# Schematic.net
KiCad netlist of a schematic drawn in Altium Designer
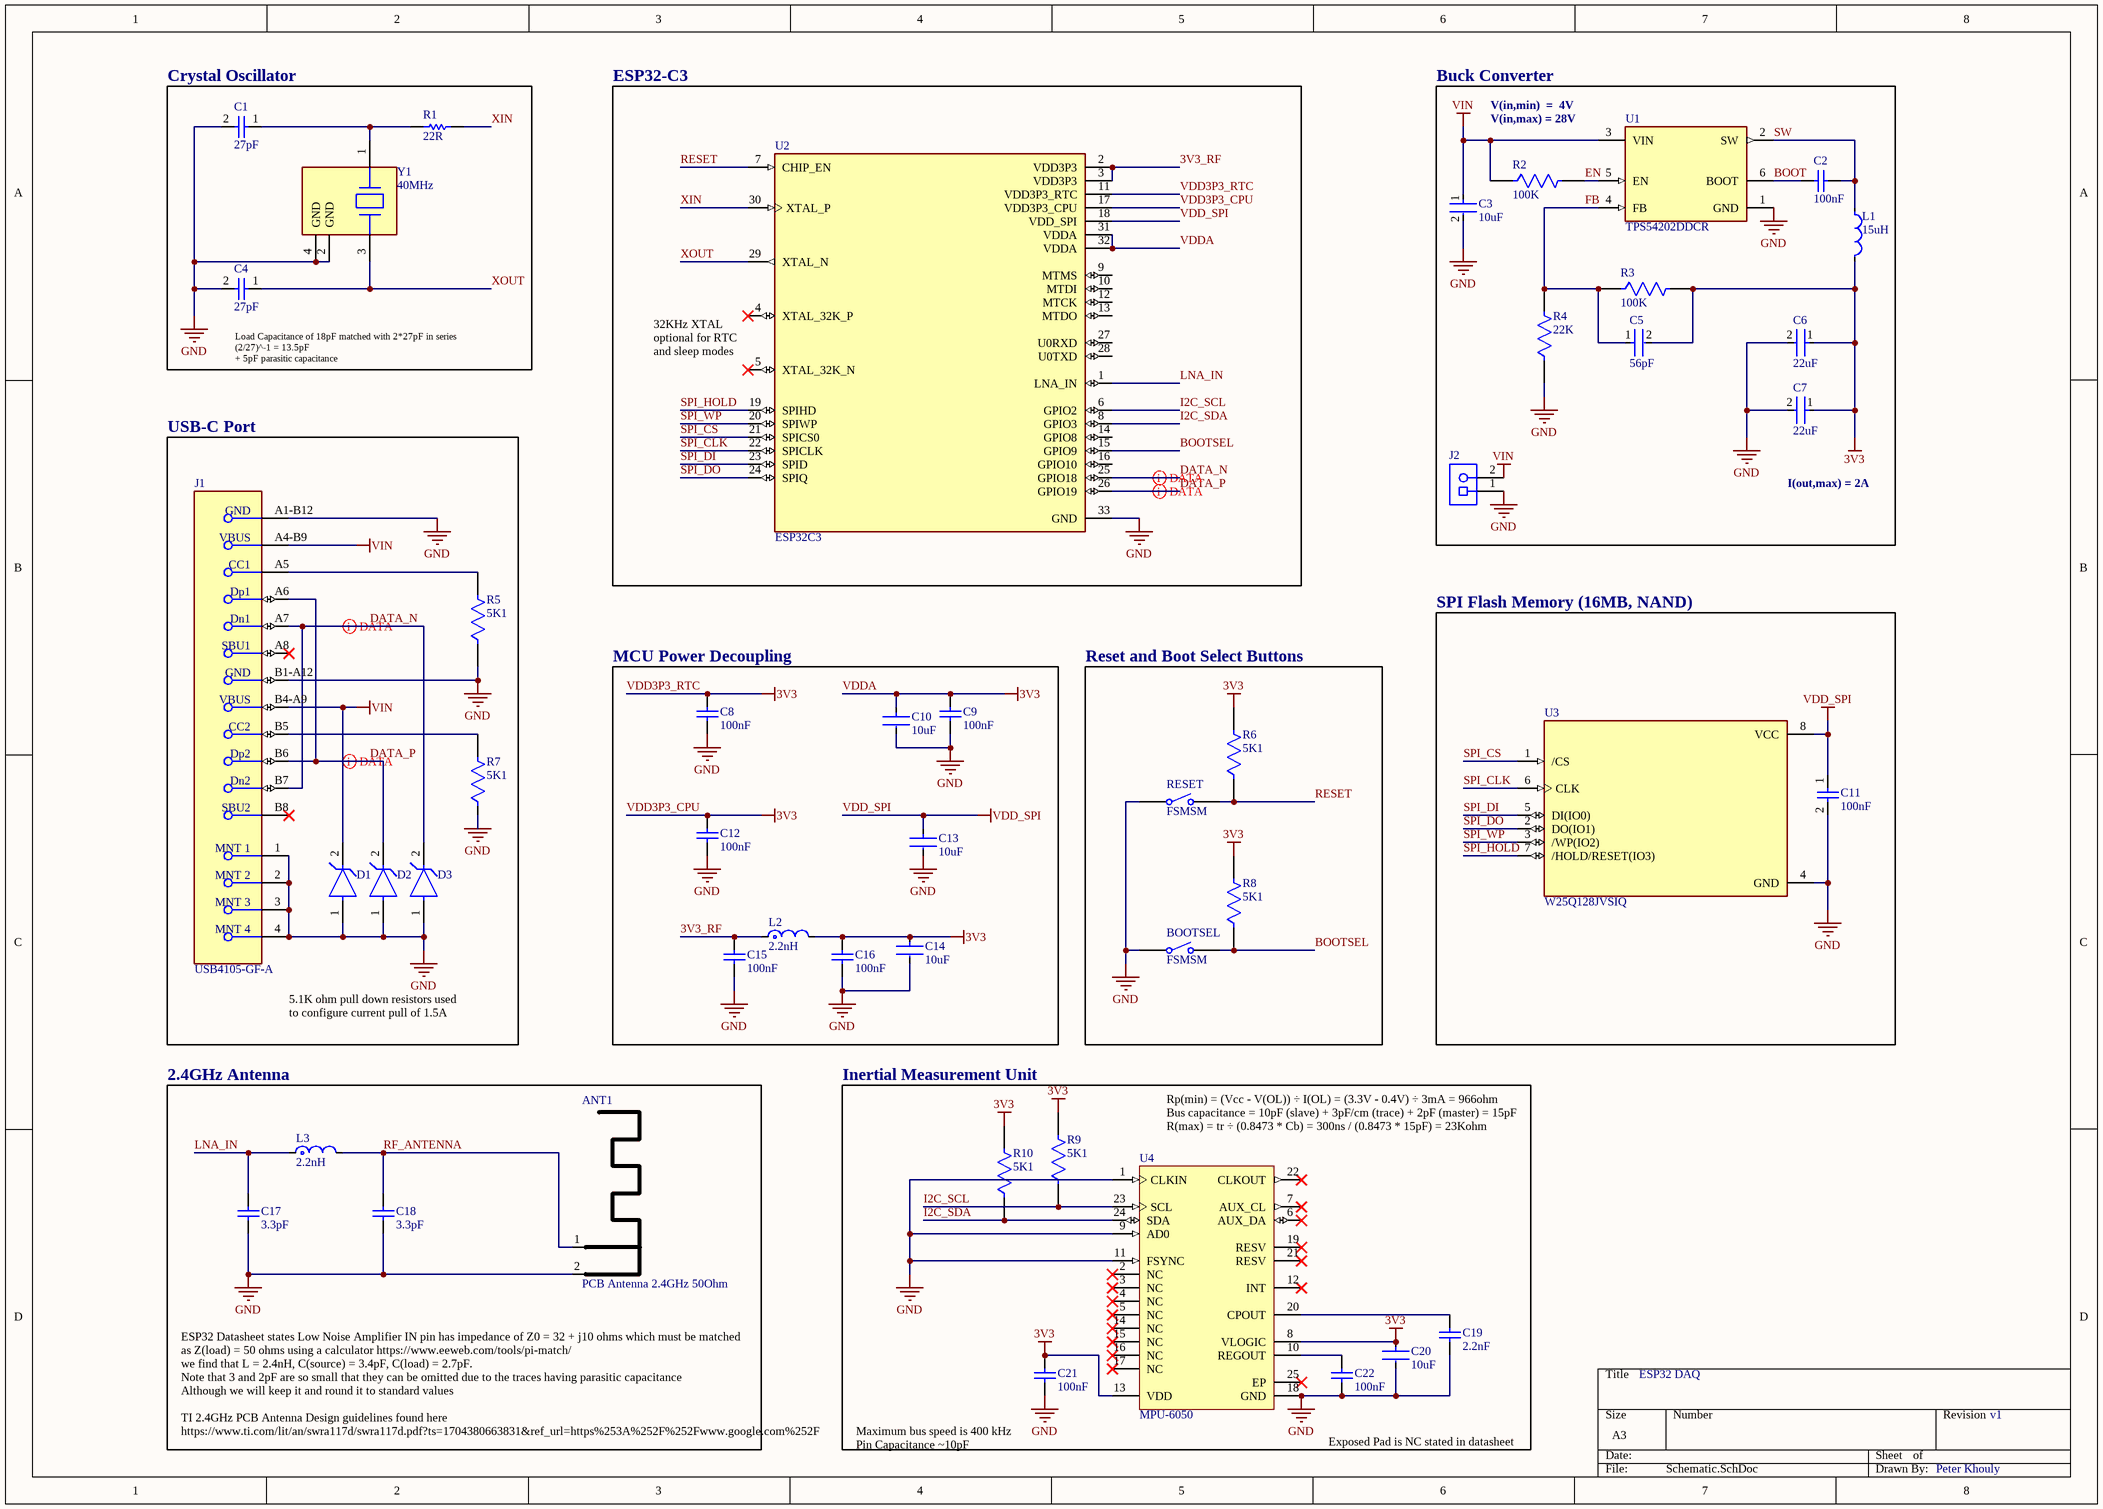
[diagram p0: Schematic.SchDoc]

(export (version "E")
  (design (tool "Eeschema 10.0.6"))
  (components
    (comp (ref "ANT1")
      (value "PCB Antenna 2.4GHz 50Ohm")
      (footprint "ANT_IFA_USB_2_4GHZ_50R")
      (description "Inverted F 2.4GHz ISM PCB Antenna 50 Ohm")
      (libsource (lib "Phils lab") (part "ANT_IFA_USB_2_4GHZ_50R"))
    )
    (comp (ref "BOOTSEL")
      (value "FSMSM")
      (footprint "TECO-FSMSM-2_V")
      (description "FSMSM Push Button Switch, 50 mA, -35 to 85 degC, 2-Pin SMD, RoHS, Bulk")
      (fields (field (name "MANUFACTURER") "TE Connectivity"))
      (libsource (lib "Altium Content Vault") (part "SW-SPST-2_C"))
    )
    (comp (ref "C1")
      (value "27pF")
      (footprint "CAPC1005X55X25LL05T10")
      (fields (field (name "PART NUMBER") "GRM1555C1H270JA01D") (field (name "MANUFACTURER") "Murata"))
      (libsource (lib "") (part "CAP_1"))
    )
    (comp (ref "C2")
      (value "100nF")
      (footprint "CAPC1005X56X25LL10T15")
      (fields
        (field (name "MANUFACTURER") "AVX Interconnect / Elco")
        (field (name "PART NUMBER") "04026D104KAT2A")
      )
      (libsource (lib "Altium Content Vault") (part "CAP"))
    )
    (comp (ref "C3")
      (value "10uF")
      (footprint "FP-GRM15-0_2-MFG")
      (description "CAP CER 10UF 6.3V X6S 0402")
      (fields (field (name "TOLERANCE") "20%") (field (name "MANUFACTURER PART NUMBER") "GRM155C80J106ME11D"))
      (libsource (lib "") (part "b4654b650e69147ec39a6b967a45e02_1"))
    )
    (comp (ref "C4")
      (value "27pF")
      (footprint "CAPC1005X55X25LL05T10")
      (fields (field (name "PART NUMBER") "GRM1555C1H270JA01D") (field (name "MANUFACTURER") "Murata"))
      (libsource (lib "") (part "CAP_1"))
    )
    (comp (ref "C5")
      (value "56pF")
      (footprint "FP-0402-L_1_0_1-W_0_5_0_1-MFG")
      (description "General Purpose Ceramic Capacitor, 0402, 56pF, 5%, C0G, 30ppm/°C, 50V")
      (fields (field (name "TOLERANCE") "5%") (field (name "VOLTAGE") "50V"))
      (libsource (lib "") (part "b4654b650e69147ec39a6b967a45e02_1"))
    )
    (comp (ref "C6")
      (value "22uF")
      (footprint "FP-CL746-IPC_C")
      (description "Cap Ceramic 22uF 6.3V X5R ±20% SMD 0402 +85°C Paper T/R")
      (fields (field (name "TOLERANCE") "20%"))
      (libsource (lib "") (part "b4654b650e69147ec39a6b967a45e02_1"))
    )
    (comp (ref "C7")
      (value "22uF")
      (footprint "FP-CL746-IPC_C")
      (description "Cap Ceramic 22uF 6.3V X5R ±20% SMD 0402 +85°C Paper T/R")
      (fields (field (name "TOLERANCE") "20%"))
      (libsource (lib "") (part "b4654b650e69147ec39a6b967a45e02_1"))
    )
    (comp (ref "C8")
      (value "100nF")
      (footprint "CAPC1005X56X25LL10T15")
      (fields
        (field (name "MANUFACTURER") "AVX Interconnect / Elco")
        (field (name "PART NUMBER") "04026D104KAT2A")
      )
      (libsource (lib "Altium Content Vault") (part "CAP"))
    )
    (comp (ref "C9")
      (value "100nF")
      (footprint "CAPC1005X56X25LL10T15")
      (fields
        (field (name "MANUFACTURER") "AVX Interconnect / Elco")
        (field (name "PART NUMBER") "04026D104KAT2A")
      )
      (libsource (lib "Altium Content Vault") (part "CAP"))
    )
    (comp (ref "C10")
      (value "10uF")
      (footprint "FP-GRM15-0_2-MFG")
      (description "CAP CER 10UF 6.3V X6S 0402")
      (fields (field (name "TOLERANCE") "20%") (field (name "MANUFACTURER PART NUMBER") "GRM155C80J106ME11D"))
      (libsource (lib "Altium Content Vault") (part "b4654b650e69147ec39a6b967a45e02"))
    )
    (comp (ref "C11")
      (value "100nF")
      (footprint "CAPC1005X56X25LL10T15")
      (fields
        (field (name "MANUFACTURER") "AVX Interconnect / Elco")
        (field (name "PART NUMBER") "04026D104KAT2A")
      )
      (libsource (lib "") (part "CAP_1"))
    )
    (comp (ref "C12")
      (value "100nF")
      (footprint "CAPC1005X56X25LL10T15")
      (fields
        (field (name "MANUFACTURER") "AVX Interconnect / Elco")
        (field (name "PART NUMBER") "04026D104KAT2A")
      )
      (libsource (lib "Altium Content Vault") (part "CAP"))
    )
    (comp (ref "C13")
      (value "10uF")
      (footprint "FP-GRM15-0_2-MFG")
      (description "CAP CER 10UF 6.3V X6S 0402")
      (fields (field (name "TOLERANCE") "20%") (field (name "MANUFACTURER PART NUMBER") "GRM155C80J106ME11D"))
      (libsource (lib "Altium Content Vault") (part "b4654b650e69147ec39a6b967a45e02"))
    )
    (comp (ref "C14")
      (value "10uF")
      (footprint "FP-GRM15-0_2-MFG")
      (description "CAP CER 10UF 6.3V X6S 0402")
      (fields (field (name "TOLERANCE") "20%") (field (name "MANUFACTURER PART NUMBER") "GRM155C80J106ME11D"))
      (libsource (lib "Altium Content Vault") (part "b4654b650e69147ec39a6b967a45e02"))
    )
    (comp (ref "C15")
      (value "100nF")
      (footprint "CAPC1005X56X25LL10T15")
      (fields
        (field (name "MANUFACTURER") "AVX Interconnect / Elco")
        (field (name "PART NUMBER") "04026D104KAT2A")
      )
      (libsource (lib "Altium Content Vault") (part "CAP"))
    )
    (comp (ref "C16")
      (value "100nF")
      (footprint "CAPC1005X56X25LL10T15")
      (fields
        (field (name "MANUFACTURER") "AVX Interconnect / Elco")
        (field (name "PART NUMBER") "04026D104KAT2A")
      )
      (libsource (lib "Altium Content Vault") (part "CAP"))
    )
    (comp (ref "C17")
      (value "3.3pF")
      (footprint "CAPC1005X55X25NL5T10")
      (fields (field (name "PARTNUMBER") "GRM1555C1H3R3CA01D"))
      (libsource (lib "Altium Content Vault") (part "CAP-NP-2"))
    )
    (comp (ref "C18")
      (value "3.3pF")
      (footprint "CAPC1005X55X25NL5T10")
      (fields (field (name "PARTNUMBER") "GRM1555C1H3R3CA01D"))
      (libsource (lib "Altium Content Vault") (part "CAP-NP-2"))
    )
    (comp (ref "C19")
      (value "2.2nF")
      (footprint "CAPC1005X56X25LL10T15")
      (fields
        (field (name "MANUFACTURER") "AVX Interconnect / Elco")
        (field (name "PART NUMBER") "04025C222JAT2A")
      )
      (libsource (lib "Altium Content Vault") (part "CAP"))
    )
    (comp (ref "C20")
      (value "10uF")
      (footprint "FP-GRM15-0_2-MFG")
      (description "CAP CER 10UF 6.3V X6S 0402")
      (fields (field (name "TOLERANCE") "20%") (field (name "MANUFACTURER PART NUMBER") "GRM155C80J106ME11D"))
      (libsource (lib "Altium Content Vault") (part "b4654b650e69147ec39a6b967a45e02"))
    )
    (comp (ref "C21")
      (value "100nF")
      (footprint "CAPC1005X56X25LL10T15")
      (fields
        (field (name "MANUFACTURER") "AVX Interconnect / Elco")
        (field (name "PART NUMBER") "04026D104KAT2A")
      )
      (libsource (lib "Altium Content Vault") (part "CAP"))
    )
    (comp (ref "C22")
      (value "100nF")
      (footprint "CAPC1005X56X25LL10T15")
      (fields
        (field (name "MANUFACTURER") "AVX Interconnect / Elco")
        (field (name "PART NUMBER") "04026D104KAT2A")
      )
      (libsource (lib "Altium Content Vault") (part "CAP"))
    )
    (comp (ref "D1")
      (value "~")
      (footprint "FP-SLP1006P2-MFG")
      (description "TVS DIODE 33VWM 60VC SLP1006P2")
      (libsource (lib "Altium Content Vault") (part "3fba79ac723ca0a4e69928609483429"))
    )
    (comp (ref "D2")
      (value "~")
      (footprint "FP-SLP1006P2-MFG")
      (description "TVS DIODE 33VWM 60VC SLP1006P2")
      (libsource (lib "Altium Content Vault") (part "3fba79ac723ca0a4e69928609483429"))
    )
    (comp (ref "D3")
      (value "~")
      (footprint "FP-SLP1006P2-MFG")
      (description "TVS DIODE 33VWM 60VC SLP1006P2")
      (libsource (lib "Altium Content Vault") (part "3fba79ac723ca0a4e69928609483429"))
    )
    (comp (ref "J1")
      (value "USB4105-GF-A")
      (footprint "FP-USB4105-GF-A-MFG")
      (description "CONN RCPT USB2.0 TYPEC 5A")
      (fields
        (field (name "MANUFACTURER") "GCT")
        (field (name "OCTOPART") "https://octopart.com/usb4105-gf-a-gct-106627878")
      )
      (libsource (lib "Altium Content Vault") (part "e7c17a616881a82b79941196b4bec10"))
    )
    (comp (ref "J2")
      (value "~")
      (footprint "PHOE-1729128-2_V")
      (description "PCB Terminal Block, 13.5 A, 400 V, 2-Pin THD, RoHS, Bulk")
      (fields (field (name "PARTNUMBER") "1729128") (field (name "MANUFACTURER") "Phoenix Contact"))
      (libsource (lib "Altium Content Vault") (part "CN-2P-F-R2"))
    )
    (comp (ref "L1")
      (value "15uH")
      (footprint "FP-MLZ2012-1_25-IPC_B")
      (description "Shielded Multilayer Inductor 15uH ±20% 350mA 611mΩ SMD 0805")
      (fields (field (name "TOLERANCE") "20%"))
      (libsource (lib "Altium Content Vault") (part "725321dda6339637d4d059423bc1c3c"))
    )
    (comp (ref "L2")
      (value "2.2nH")
      (footprint "FP-LQG15HH_02-IPC_C")
      (description "Multilayer type RF Inductor 2.2nH ±0.3nH 0.09Ω 900mA 0402")
      (libsource (lib "Altium Content Vault") (part "4cc4b267dca4c8e51f7102f422741d8"))
    )
    (comp (ref "L3")
      (value "2.2nH")
      (footprint "FP-LQG15HH_02-IPC_C")
      (description "Multilayer type RF Inductor 2.2nH ±0.3nH 0.09Ω 900mA 0402")
      (libsource (lib "Altium Content Vault") (part "4cc4b267dca4c8e51f7102f422741d8"))
    )
    (comp (ref "R1")
      (value "22R")
      (footprint "RESC1005X40X25ML05T05")
      (description "Chip Resistor, 22 Ohm, +/- 1%, 0.1 W, -55 to 155 degC, 0402 (1005 Metric), RoHS, Tape and Reel")
      (fields (field (name "PARTNUMBER") "ERJ-2RKF22R0X") (field (name "TOLERANCE") "1%"))
      (libsource (lib "Altium Content Vault") (part "RES-2"))
    )
    (comp (ref "R2")
      (value "100K")
      (footprint "FP-ERJ2RK-IPC_C")
      (description "RES SMD 100K OHM 1% 1/10W 0402")
      (fields (field (name "TOLERANCE") "1%"))
      (libsource (lib "Altium Content Vault") (part "1029c3af85768c4190bb7ad29bc67b5"))
    )
    (comp (ref "R3")
      (value "100K")
      (footprint "FP-ERJ2RK-IPC_C")
      (description "RES SMD 100K OHM 1% 1/10W 0402")
      (fields (field (name "TOLERANCE") "1%"))
      (libsource (lib "Altium Content Vault") (part "1029c3af85768c4190bb7ad29bc67b5"))
    )
    (comp (ref "R4")
      (value "22K")
      (footprint "FP-ERJ2RK-MFG")
      (description "RES SMD 22K OHM 1% 1/10W 0402")
      (fields (field (name "TOLERANCE") "1%"))
      (libsource (lib "Altium Content Vault") (part "1029c3af85768c4190bb7ad29bc67b5"))
    )
    (comp (ref "R5")
      (value "5K1")
      (footprint "FP-ERJ2RK-IPC_A")
      (description "RES SMD 5.1K OHM 1% 1/10W 0402")
      (fields (field (name "TOLERANCE") "1%"))
      (libsource (lib "Altium Content Vault") (part "1029c3af85768c4190bb7ad29bc67b5"))
    )
    (comp (ref "R6")
      (value "5K1")
      (footprint "FP-ERJ2RK-IPC_A")
      (description "RES SMD 5.1K OHM 1% 1/10W 0402")
      (fields (field (name "TOLERANCE") "1%"))
      (libsource (lib "Altium Content Vault") (part "1029c3af85768c4190bb7ad29bc67b5"))
    )
    (comp (ref "R7")
      (value "5K1")
      (footprint "FP-ERJ2RK-IPC_A")
      (description "RES SMD 5.1K OHM 1% 1/10W 0402")
      (fields (field (name "TOLERANCE") "1%"))
      (libsource (lib "Altium Content Vault") (part "1029c3af85768c4190bb7ad29bc67b5"))
    )
    (comp (ref "R8")
      (value "5K1")
      (footprint "FP-ERJ2RK-IPC_A")
      (description "RES SMD 5.1K OHM 1% 1/10W 0402")
      (fields (field (name "TOLERANCE") "1%"))
      (libsource (lib "Altium Content Vault") (part "1029c3af85768c4190bb7ad29bc67b5"))
    )
    (comp (ref "R9")
      (value "5K1")
      (footprint "FP-ERJ2RK-IPC_A")
      (description "RES SMD 5.1K OHM 1% 1/10W 0402")
      (fields (field (name "TOLERANCE") "1%"))
      (libsource (lib "Altium Content Vault") (part "1029c3af85768c4190bb7ad29bc67b5"))
    )
    (comp (ref "R10")
      (value "5K1")
      (footprint "FP-ERJ2RK-IPC_A")
      (description "RES SMD 5.1K OHM 1% 1/10W 0402")
      (fields (field (name "TOLERANCE") "1%"))
      (libsource (lib "Altium Content Vault") (part "1029c3af85768c4190bb7ad29bc67b5"))
    )
    (comp (ref "RESET")
      (value "FSMSM")
      (footprint "TECO-FSMSM-2_V")
      (description "FSMSM Push Button Switch, 50 mA, -35 to 85 degC, 2-Pin SMD, RoHS, Bulk")
      (fields (field (name "MANUFACTURER") "TE Connectivity"))
      (libsource (lib "Altium Content Vault") (part "SW-SPST-2_C"))
    )
    (comp (ref "U1")
      (value "TPS54202DDCR")
      (footprint "FP-DDC0006A-IPC_B")
      (description "IC REG BUCK ADJ 2A TSOT23-6")
      (libsource (lib "Altium Content Vault") (part "35c2d3f1afc239a386b2ba50eead654"))
    )
    (comp (ref "U2")
      (value "ESP32C3")
      (footprint "QFN32_5X5MM")
      (fields (field (name "MF") "Espressif Systems") (field (name "MP") "ESP32-C3"))
      (libsource (lib "ESP32C3") (part "ESP32C3"))
    )
    (comp (ref "U3")
      (value "W25Q128JVSIQ")
      (footprint "SOIC127P790X216-8N")
      (description "FLASH - NOR Memory IC 128Mb (16M x 8) SPI - Quad I/O, QPI, DTR 133 MHz 8-SOIC")
      (fields (field (name "MF") "Winbond Electronics"))
      (libsource (lib "W25Q128JVSIQ") (part "W25Q128JVSIQ"))
    )
    (comp (ref "U4")
      (value "MPU-6050")
      (footprint "IS-QFN-24_V")
      (fields (field (name "MANUFACTURER") "InvenSense"))
      (libsource (lib "Altium Content Vault") (part "IS-MPU-6050-QFN-24"))
    )
    (comp (ref "Y1")
      (value "40MHz")
      (footprint "FP-ABM3B-MFG")
      (description "Crystal 40MHz ±20ppm 18pF SMD-4 5mm x 3.2mm")
      (fields (field (name "TOLERANCE") "20ppm"))
      (libsource (lib "Altium Content Vault") (part "48e526d86b7f2615d98721063c72f49"))
    )
  )
  (nets
    (net (code "1") (name "/3V3_RF") (class "Default")
      (node (ref "C15") (pin "1") (pinfunction "1_1") (pintype "passive"))
      (node (ref "L2") (pin "1") (pinfunction "1_1") (pintype "passive"))
      (node (ref "U2") (pin "2") (pinfunction "VDD3P3_2") (pintype "power_in"))
      (node (ref "U2") (pin "3") (pinfunction "VDD3P3_3") (pintype "power_in"))
    )
    (net (code "2") (name "/BOOT") (class "Default")
      (node (ref "C2") (pin "2") (pinfunction "2_2") (pintype "passive"))
      (node (ref "U1") (pin "6") (pinfunction "BOOT_6") (pintype "passive"))
    )
    (net (code "3") (name "/BOOTSEL") (class "Default")
      (node (ref "BOOTSEL") (pin "2") (pinfunction "2_2") (pintype "passive"))
      (node (ref "R8") (pin "1") (pinfunction "1_1") (pintype "passive"))
      (node (ref "U2") (pin "15") (pinfunction "GPIO9_15") (pintype "bidirectional"))
    )
    (net (code "4") (name "/DATA_N") (class "Default")
      (node (ref "D3") (pin "2") (pinfunction "C_2") (pintype "passive"))
      (node (ref "J1") (pin "A7") (pinfunction "Dn1_A7") (pintype "bidirectional"))
      (node (ref "J1") (pin "B7") (pinfunction "Dn2_B7") (pintype "bidirectional"))
      (node (ref "U2") (pin "25") (pinfunction "GPIO18_25") (pintype "bidirectional"))
    )
    (net (code "5") (name "/DATA_P") (class "Default")
      (node (ref "D2") (pin "2") (pinfunction "C_2") (pintype "passive"))
      (node (ref "J1") (pin "A6") (pinfunction "Dp1_A6") (pintype "bidirectional"))
      (node (ref "J1") (pin "B6") (pinfunction "Dp2_B6") (pintype "bidirectional"))
      (node (ref "U2") (pin "26") (pinfunction "GPIO19_26") (pintype "bidirectional"))
    )
    (net (code "6") (name "/EN") (class "Default")
      (node (ref "R2") (pin "2") (pinfunction "2_2") (pintype "passive"))
      (node (ref "U1") (pin "5") (pinfunction "EN_5") (pintype "input"))
    )
    (net (code "7") (name "/FB") (class "Default")
      (node (ref "C5") (pin "1") (pinfunction "1_1") (pintype "passive"))
      (node (ref "R3") (pin "1") (pinfunction "1_1") (pintype "passive"))
      (node (ref "R4") (pin "2") (pinfunction "2_2") (pintype "passive"))
      (node (ref "U1") (pin "4") (pinfunction "FB_4") (pintype "input"))
    )
    (net (code "8") (name "/I2C_SCL") (class "Default")
      (node (ref "R9") (pin "1") (pinfunction "1_1") (pintype "passive"))
      (node (ref "U2") (pin "6") (pinfunction "GPIO2_6") (pintype "bidirectional"))
      (node (ref "U4") (pin "23") (pinfunction "SCL_23") (pintype "input"))
    )
    (net (code "9") (name "/I2C_SDA") (class "Default")
      (node (ref "R10") (pin "1") (pinfunction "1_1") (pintype "passive"))
      (node (ref "U2") (pin "8") (pinfunction "GPIO3_8") (pintype "bidirectional"))
      (node (ref "U4") (pin "24") (pinfunction "SDA_24") (pintype "bidirectional"))
    )
    (net (code "10") (name "/LNA_IN") (class "Default")
      (node (ref "C17") (pin "2") (pinfunction "2_2") (pintype "passive"))
      (node (ref "L3") (pin "1") (pinfunction "1_1") (pintype "passive"))
      (node (ref "U2") (pin "1") (pinfunction "LNA_IN_1") (pintype "bidirectional"))
    )
    (net (code "11") (name "/RESET") (class "Default")
      (node (ref "R6") (pin "1") (pinfunction "1_1") (pintype "passive"))
      (node (ref "RESET") (pin "2") (pinfunction "2_2") (pintype "passive"))
      (node (ref "U2") (pin "7") (pinfunction "CHIP_EN_7") (pintype "input"))
    )
    (net (code "12") (name "/RF_ANTENNA") (class "Default")
      (node (ref "ANT1") (pin "1") (pinfunction "RF_1") (pintype "passive"))
      (node (ref "C18") (pin "2") (pinfunction "2_2") (pintype "passive"))
      (node (ref "L3") (pin "2") (pinfunction "2_2") (pintype "passive"))
    )
    (net (code "13") (name "/SPI_CLK") (class "Default")
      (node (ref "U2") (pin "22") (pinfunction "SPICLK_22") (pintype "bidirectional"))
      (node (ref "U3") (pin "6") (pinfunction "CLK_6") (pintype "input"))
    )
    (net (code "14") (name "/SPI_CS") (class "Default")
      (node (ref "U2") (pin "21") (pinfunction "SPICS0_21") (pintype "bidirectional"))
      (node (ref "U3") (pin "1") (pinfunction "/CS_1") (pintype "input"))
    )
    (net (code "15") (name "/SPI_DI") (class "Default")
      (node (ref "U2") (pin "23") (pinfunction "SPID_23") (pintype "bidirectional"))
      (node (ref "U3") (pin "5") (pinfunction "DI(IO0)_5") (pintype "bidirectional"))
    )
    (net (code "16") (name "/SPI_DO") (class "Default")
      (node (ref "U2") (pin "24") (pinfunction "SPIQ_24") (pintype "bidirectional"))
      (node (ref "U3") (pin "2") (pinfunction "DO(IO1)_2") (pintype "bidirectional"))
    )
    (net (code "17") (name "/SPI_HOLD") (class "Default")
      (node (ref "U2") (pin "19") (pinfunction "SPIHD_19") (pintype "bidirectional"))
      (node (ref "U3") (pin "7") (pinfunction "/HOLD/RESET(IO3)_7") (pintype "bidirectional"))
    )
    (net (code "18") (name "/SPI_WP") (class "Default")
      (node (ref "U2") (pin "20") (pinfunction "SPIWP_20") (pintype "bidirectional"))
      (node (ref "U3") (pin "3") (pinfunction "/WP(IO2)_3") (pintype "bidirectional"))
    )
    (net (code "19") (name "/SW") (class "Default")
      (node (ref "C2") (pin "1") (pinfunction "1_1") (pintype "passive"))
      (node (ref "L1") (pin "1") (pinfunction "1_1") (pintype "passive"))
      (node (ref "U1") (pin "2") (pinfunction "SW_2") (pintype "output"))
    )
    (net (code "20") (name "/XIN") (class "Default")
      (node (ref "R1") (pin "2") (pinfunction "2_2") (pintype "passive"))
      (node (ref "U2") (pin "30") (pinfunction "XTAL_P_30") (pintype "input"))
    )
    (net (code "21") (name "/XOUT") (class "Default")
      (node (ref "C4") (pin "1") (pinfunction "1_1") (pintype "passive"))
      (node (ref "U2") (pin "29") (pinfunction "XTAL_N_29") (pintype "output"))
      (node (ref "Y1") (pin "3") (pinfunction "3_3") (pintype "passive"))
    )
    (net (code "22") (name "3V3") (class "Default")
      (node (ref "C10") (pin "1") (pinfunction "1_1") (pintype "passive"))
      (node (ref "C12") (pin "1") (pinfunction "1_1") (pintype "passive"))
      (node (ref "C14") (pin "1") (pinfunction "1_1") (pintype "passive"))
      (node (ref "C16") (pin "1") (pinfunction "1_1") (pintype "passive"))
      (node (ref "C20") (pin "1") (pinfunction "1_1") (pintype "passive"))
      (node (ref "C21") (pin "1") (pinfunction "1_1") (pintype "passive"))
      (node (ref "C5") (pin "2") (pinfunction "2_2") (pintype "passive"))
      (node (ref "C6") (pin "1") (pinfunction "1_1") (pintype "passive"))
      (node (ref "C7") (pin "1") (pinfunction "1_1") (pintype "passive"))
      (node (ref "C8") (pin "1") (pinfunction "1_1") (pintype "passive"))
      (node (ref "C9") (pin "1") (pinfunction "1_1") (pintype "passive"))
      (node (ref "L1") (pin "2") (pinfunction "2_2") (pintype "passive"))
      (node (ref "L2") (pin "2") (pinfunction "2_2") (pintype "passive"))
      (node (ref "R10") (pin "2") (pinfunction "2_2") (pintype "passive"))
      (node (ref "R3") (pin "2") (pinfunction "2_2") (pintype "passive"))
      (node (ref "R6") (pin "2") (pinfunction "2_2") (pintype "passive"))
      (node (ref "R8") (pin "2") (pinfunction "2_2") (pintype "passive"))
      (node (ref "R9") (pin "2") (pinfunction "2_2") (pintype "passive"))
      (node (ref "U2") (pin "11") (pinfunction "VDD3P3_RTC_11") (pintype "power_in"))
      (node (ref "U2") (pin "17") (pinfunction "VDD3P3_CPU_17") (pintype "power_in"))
      (node (ref "U2") (pin "31") (pinfunction "VDDA_31") (pintype "power_in"))
      (node (ref "U2") (pin "32") (pinfunction "VDDA_32") (pintype "power_in"))
      (node (ref "U4") (pin "13") (pinfunction "VDD_13") (pintype "power_in"))
      (node (ref "U4") (pin "8") (pinfunction "VLOGIC_8") (pintype "power_in"))
    )
    (net (code "23") (name "GND") (class "Default")
      (node (ref "ANT1") (pin "2") (pinfunction "GND_2") (pintype "passive"))
      (node (ref "BOOTSEL") (pin "1") (pinfunction "1_1") (pintype "passive"))
      (node (ref "C1") (pin "2") (pinfunction "2_2") (pintype "passive"))
      (node (ref "C10") (pin "2") (pinfunction "2_2") (pintype "passive"))
      (node (ref "C11") (pin "2") (pinfunction "2_2") (pintype "passive"))
      (node (ref "C12") (pin "2") (pinfunction "2_2") (pintype "passive"))
      (node (ref "C13") (pin "2") (pinfunction "2_2") (pintype "passive"))
      (node (ref "C14") (pin "2") (pinfunction "2_2") (pintype "passive"))
      (node (ref "C15") (pin "2") (pinfunction "2_2") (pintype "passive"))
      (node (ref "C16") (pin "2") (pinfunction "2_2") (pintype "passive"))
      (node (ref "C17") (pin "1") (pinfunction "1_1") (pintype "passive"))
      (node (ref "C18") (pin "1") (pinfunction "1_1") (pintype "passive"))
      (node (ref "C19") (pin "2") (pinfunction "2_2") (pintype "passive"))
      (node (ref "C20") (pin "2") (pinfunction "2_2") (pintype "passive"))
      (node (ref "C21") (pin "2") (pinfunction "2_2") (pintype "passive"))
      (node (ref "C22") (pin "2") (pinfunction "2_2") (pintype "passive"))
      (node (ref "C3") (pin "2") (pinfunction "2_2") (pintype "passive"))
      (node (ref "C4") (pin "2") (pinfunction "2_2") (pintype "passive"))
      (node (ref "C6") (pin "2") (pinfunction "2_2") (pintype "passive"))
      (node (ref "C7") (pin "2") (pinfunction "2_2") (pintype "passive"))
      (node (ref "C8") (pin "2") (pinfunction "2_2") (pintype "passive"))
      (node (ref "C9") (pin "2") (pinfunction "2_2") (pintype "passive"))
      (node (ref "D1") (pin "1") (pinfunction "A_1") (pintype "passive"))
      (node (ref "D2") (pin "1") (pinfunction "A_1") (pintype "passive"))
      (node (ref "D3") (pin "1") (pinfunction "A_1") (pintype "passive"))
      (node (ref "J1") (pin "1") (pinfunction "MNT_1_1") (pintype "power_in"))
      (node (ref "J1") (pin "2") (pinfunction "MNT_2_2") (pintype "power_in"))
      (node (ref "J1") (pin "3") (pinfunction "MNT_3_3") (pintype "power_in"))
      (node (ref "J1") (pin "4") (pinfunction "MNT_4_4") (pintype "power_in"))
      (node (ref "J1") (pin "A1-B12") (pinfunction "GND_A1-B12") (pintype "power_in"))
      (node (ref "J1") (pin "B1-A12") (pinfunction "GND_B1-A12") (pintype "bidirectional"))
      (node (ref "J2") (pin "1") (pinfunction "1_1") (pintype "passive"))
      (node (ref "R4") (pin "1") (pinfunction "1_1") (pintype "passive"))
      (node (ref "R5") (pin "1") (pinfunction "1_1") (pintype "passive"))
      (node (ref "R7") (pin "1") (pinfunction "1_1") (pintype "passive"))
      (node (ref "RESET") (pin "1") (pinfunction "1_1") (pintype "passive"))
      (node (ref "U1") (pin "1") (pinfunction "GND_1") (pintype "power_in"))
      (node (ref "U2") (pin "33") (pinfunction "GND_33") (pintype "power_in"))
      (node (ref "U3") (pin "4") (pinfunction "GND_4") (pintype "power_in"))
      (node (ref "U4") (pin "1") (pinfunction "CLKIN_1") (pintype "input"))
      (node (ref "U4") (pin "11") (pinfunction "FSYNC_11") (pintype "input"))
      (node (ref "U4") (pin "18") (pinfunction "GND_18") (pintype "power_in"))
      (node (ref "U4") (pin "9") (pinfunction "AD0_9") (pintype "input"))
      (node (ref "Y1") (pin "2") (pinfunction "GND_2") (pintype "power_in"))
      (node (ref "Y1") (pin "4") (pinfunction "GND_4") (pintype "power_in"))
    )
    (net (code "24") (name "Net-(C1-Pad1)") (class "Default")
      (node (ref "C1") (pin "1") (pinfunction "1_1") (pintype "passive"))
      (node (ref "R1") (pin "1") (pinfunction "1_1") (pintype "passive"))
      (node (ref "Y1") (pin "1") (pinfunction "1_1") (pintype "passive"))
    )
    (net (code "25") (name "Net-(J1-CC1)") (class "Default")
      (node (ref "J1") (pin "A5") (pinfunction "CC1_A5") (pintype "power_in"))
      (node (ref "R5") (pin "2") (pinfunction "2_2") (pintype "passive"))
    )
    (net (code "26") (name "Net-(J1-CC2)") (class "Default")
      (node (ref "J1") (pin "B5") (pinfunction "CC2_B5") (pintype "bidirectional"))
      (node (ref "R7") (pin "2") (pinfunction "2_2") (pintype "passive"))
    )
    (net (code "27") (name "Net-(U4-CPOUT)") (class "Default")
      (node (ref "C19") (pin "1") (pinfunction "1_1") (pintype "passive"))
      (node (ref "U4") (pin "20") (pinfunction "CPOUT_20") (pintype "passive"))
    )
    (net (code "28") (name "Net-(U4-REGOUT)") (class "Default")
      (node (ref "C22") (pin "1") (pinfunction "1_1") (pintype "passive"))
      (node (ref "U4") (pin "10") (pinfunction "REGOUT_10") (pintype "passive"))
    )
    (net (code "29") (name "VDD_SPI") (class "Default")
      (node (ref "C11") (pin "1") (pinfunction "1_1") (pintype "passive"))
      (node (ref "C13") (pin "1") (pinfunction "1_1") (pintype "passive"))
      (node (ref "U2") (pin "18") (pinfunction "VDD_SPI_18") (pintype "power_in"))
      (node (ref "U3") (pin "8") (pinfunction "VCC_8") (pintype "power_in"))
    )
    (net (code "30") (name "VIN") (class "Default")
      (node (ref "C3") (pin "1") (pinfunction "1_1") (pintype "passive"))
      (node (ref "D1") (pin "2") (pinfunction "C_2") (pintype "passive"))
      (node (ref "J1") (pin "A4-B9") (pinfunction "VBUS_A4-B9") (pintype "power_in"))
      (node (ref "J1") (pin "B4-A9") (pinfunction "VBUS_B4-A9") (pintype "bidirectional"))
      (node (ref "J2") (pin "2") (pinfunction "2_2") (pintype "passive"))
      (node (ref "R2") (pin "1") (pinfunction "1_1") (pintype "passive"))
      (node (ref "U1") (pin "3") (pinfunction "VIN_3") (pintype "power_in"))
    )
    (net (code "31") (name "unconnected-(J1-SBU1-PadA8)") (class "Default")
      (node (ref "J1") (pin "A8") (pinfunction "SBU1_A8") (pintype "bidirectional+no_connect"))
    )
    (net (code "32") (name "unconnected-(J1-SBU2-PadB8)") (class "Default")
      (node (ref "J1") (pin "B8") (pinfunction "SBU2_B8") (pintype "power_in+no_connect"))
    )
    (net (code "33") (name "unconnected-(U2-GPIO8-Pad14)") (class "Default")
      (node (ref "U2") (pin "14") (pinfunction "GPIO8_14") (pintype "bidirectional"))
    )
    (net (code "34") (name "unconnected-(U2-GPIO10-Pad16)") (class "Default")
      (node (ref "U2") (pin "16") (pinfunction "GPIO10_16") (pintype "bidirectional"))
    )
    (net (code "35") (name "unconnected-(U2-MTCK-Pad12)") (class "Default")
      (node (ref "U2") (pin "12") (pinfunction "MTCK_12") (pintype "bidirectional"))
    )
    (net (code "36") (name "unconnected-(U2-MTDI-Pad10)") (class "Default")
      (node (ref "U2") (pin "10") (pinfunction "MTDI_10") (pintype "bidirectional"))
    )
    (net (code "37") (name "unconnected-(U2-MTDO-Pad13)") (class "Default")
      (node (ref "U2") (pin "13") (pinfunction "MTDO_13") (pintype "bidirectional"))
    )
    (net (code "38") (name "unconnected-(U2-MTMS-Pad9)") (class "Default")
      (node (ref "U2") (pin "9") (pinfunction "MTMS_9") (pintype "bidirectional"))
    )
    (net (code "39") (name "unconnected-(U2-U0RXD-Pad27)") (class "Default")
      (node (ref "U2") (pin "27") (pinfunction "U0RXD_27") (pintype "bidirectional"))
    )
    (net (code "40") (name "unconnected-(U2-U0TXD-Pad28)") (class "Default")
      (node (ref "U2") (pin "28") (pinfunction "U0TXD_28") (pintype "bidirectional"))
    )
    (net (code "41") (name "unconnected-(U2-XTAL_32K_N-Pad5)") (class "Default")
      (node (ref "U2") (pin "5") (pinfunction "XTAL_32K_N_5") (pintype "bidirectional+no_connect"))
    )
    (net (code "42") (name "unconnected-(U2-XTAL_32K_P-Pad4)") (class "Default")
      (node (ref "U2") (pin "4") (pinfunction "XTAL_32K_P_4") (pintype "bidirectional+no_connect"))
    )
    (net (code "43") (name "unconnected-(U4-AUX_CL-Pad7)") (class "Default")
      (node (ref "U4") (pin "7") (pinfunction "AUX_CL_7") (pintype "output+no_connect"))
    )
    (net (code "44") (name "unconnected-(U4-AUX_DA-Pad6)") (class "Default")
      (node (ref "U4") (pin "6") (pinfunction "AUX_DA_6") (pintype "bidirectional+no_connect"))
    )
    (net (code "45") (name "unconnected-(U4-CLKOUT-Pad22)") (class "Default")
      (node (ref "U4") (pin "22") (pinfunction "CLKOUT_22") (pintype "output+no_connect"))
    )
    (net (code "46") (name "unconnected-(U4-EP-Pad25)") (class "Default")
      (node (ref "U4") (pin "25") (pinfunction "EP_25") (pintype "power_in+no_connect"))
    )
    (net (code "47") (name "unconnected-(U4-INT-Pad12)") (class "Default")
      (node (ref "U4") (pin "12") (pinfunction "INT_12") (pintype "open_collector+no_connect"))
    )
    (net (code "48") (name "unconnected-(U4-NC-Pad2)") (class "Default")
      (node (ref "U4") (pin "2") (pinfunction "NC_2") (pintype "passive+no_connect"))
    )
    (net (code "49") (name "unconnected-(U4-NC-Pad3)") (class "Default")
      (node (ref "U4") (pin "3") (pinfunction "NC_3") (pintype "passive+no_connect"))
    )
    (net (code "50") (name "unconnected-(U4-NC-Pad4)") (class "Default")
      (node (ref "U4") (pin "4") (pinfunction "NC_4") (pintype "passive+no_connect"))
    )
    (net (code "51") (name "unconnected-(U4-NC-Pad5)") (class "Default")
      (node (ref "U4") (pin "5") (pinfunction "NC_5") (pintype "passive+no_connect"))
    )
    (net (code "52") (name "unconnected-(U4-NC-Pad14)") (class "Default")
      (node (ref "U4") (pin "14") (pinfunction "NC_14") (pintype "passive+no_connect"))
    )
    (net (code "53") (name "unconnected-(U4-NC-Pad15)") (class "Default")
      (node (ref "U4") (pin "15") (pinfunction "NC_15") (pintype "passive+no_connect"))
    )
    (net (code "54") (name "unconnected-(U4-NC-Pad16)") (class "Default")
      (node (ref "U4") (pin "16") (pinfunction "NC_16") (pintype "passive+no_connect"))
    )
    (net (code "55") (name "unconnected-(U4-NC-Pad17)") (class "Default")
      (node (ref "U4") (pin "17") (pinfunction "NC_17") (pintype "passive+no_connect"))
    )
    (net (code "56") (name "unconnected-(U4-RESV-Pad19)") (class "Default")
      (node (ref "U4") (pin "19") (pinfunction "RESV_19") (pintype "passive+no_connect"))
    )
    (net (code "57") (name "unconnected-(U4-RESV-Pad21)") (class "Default")
      (node (ref "U4") (pin "21") (pinfunction "RESV_21") (pintype "passive+no_connect"))
    )
  )
)
